# template.net
KiCad netlist of a schematic drawn in EAGLE
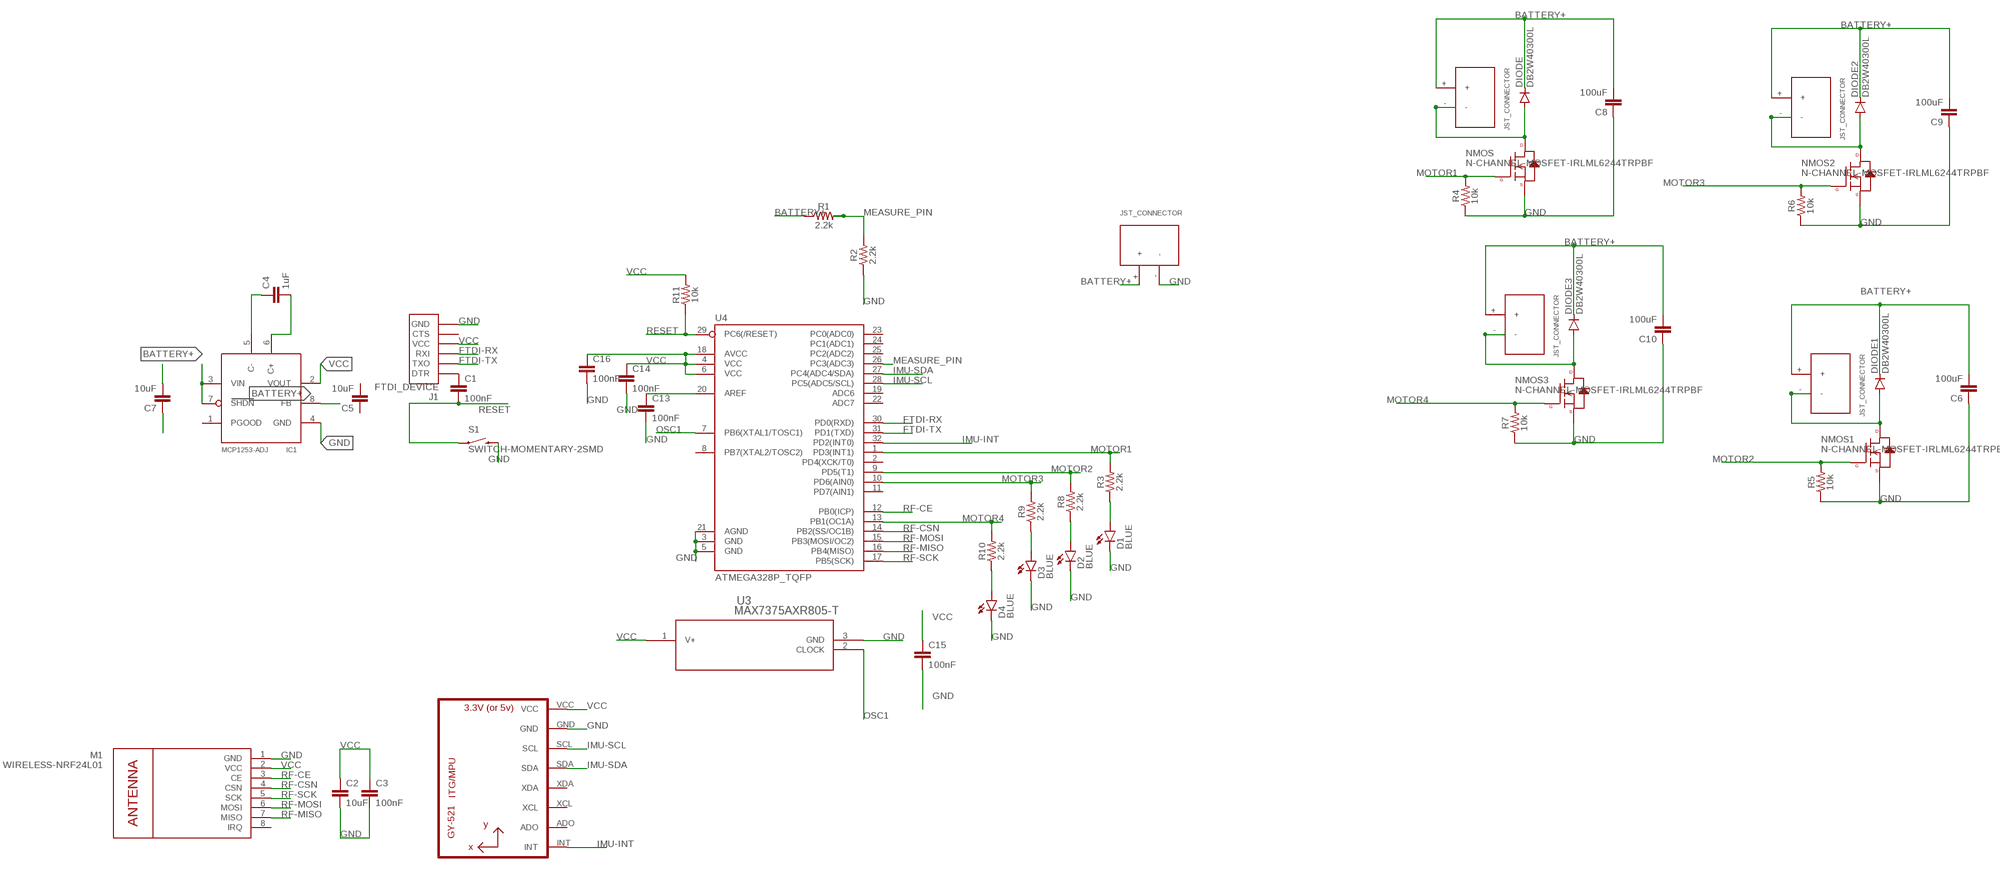
[diagram p0: schematic, sheet 1]

(export (version "E")
  (design (tool "Eeschema 10.0.6"))
  (components
    (comp (ref "C1")
      (value "100nF")
      (footprint "eagle-import:0603-CAP")
      (libsource (lib "eagle-import") (part "0.1UF-25V(+80/-20%)(0603)"))
    )
    (comp (ref "C2")
      (value "10uF")
      (footprint "eagle-import:0603-CAP")
      (libsource (lib "eagle-import") (part "CAP0603-CAP"))
    )
    (comp (ref "C3")
      (value "100nF")
      (footprint "eagle-import:0603-CAP")
      (libsource (lib "eagle-import") (part "CAP0603-CAP"))
    )
    (comp (ref "C4")
      (value "1uF")
      (footprint "eagle-import:0603-CAP")
      (libsource (lib "eagle-import") (part "0.1UF-25V(+80/-20%)(0603)"))
    )
    (comp (ref "C5")
      (value "10uF")
      (footprint "eagle-import:0603-CAP")
      (libsource (lib "eagle-import") (part "0.1UF-25V(+80/-20%)(0603)"))
    )
    (comp (ref "C6")
      (value "100uF")
      (footprint "eagle-import:1206")
      (libsource (lib "eagle-import") (part "CAP1206"))
    )
    (comp (ref "C7")
      (value "10uF")
      (footprint "eagle-import:0603-CAP")
      (libsource (lib "eagle-import") (part "0.1UF-25V(+80/-20%)(0603)"))
    )
    (comp (ref "C8")
      (value "100uF")
      (footprint "eagle-import:1206")
      (libsource (lib "eagle-import") (part "CAP1206"))
    )
    (comp (ref "C9")
      (value "100uF")
      (footprint "eagle-import:1206")
      (libsource (lib "eagle-import") (part "CAP1206"))
    )
    (comp (ref "C10")
      (value "100uF")
      (footprint "eagle-import:1206")
      (libsource (lib "eagle-import") (part "CAP1206"))
    )
    (comp (ref "C13")
      (value "100nF")
      (footprint "eagle-import:0603-CAP")
      (libsource (lib "eagle-import") (part "CAP0603-CAP"))
    )
    (comp (ref "C14")
      (value "100nF")
      (footprint "eagle-import:0603-CAP")
      (libsource (lib "eagle-import") (part "CAP0603-CAP"))
    )
    (comp (ref "C15")
      (value "100nF")
      (footprint "eagle-import:0603-CAP")
      (libsource (lib "eagle-import") (part "0.1UF-25V(+80/-20%)(0603)"))
    )
    (comp (ref "C16")
      (value "100nF")
      (footprint "eagle-import:0603-CAP")
      (libsource (lib "eagle-import") (part "CAP0603-CAP"))
    )
    (comp (ref "D1")
      (value "BLUE")
      (footprint "eagle-import:LED-0603")
      (fields (field (name "SPICEPREFIX") "D"))
      (libsource (lib "eagle-import") (part "LED-BLUE0603"))
    )
    (comp (ref "D2")
      (value "BLUE")
      (footprint "eagle-import:LED-0603")
      (libsource (lib "eagle-import") (part "LED-BLUE0603"))
    )
    (comp (ref "D3")
      (value "BLUE")
      (footprint "eagle-import:LED-0603")
      (libsource (lib "eagle-import") (part "LED-BLUE0603"))
    )
    (comp (ref "D4")
      (value "BLUE")
      (footprint "eagle-import:LED-0603")
      (libsource (lib "eagle-import") (part "LED-BLUE0603"))
    )
    (comp (ref "DIODE")
      (value "DB2W40300L")
      (footprint "eagle-import:MINI2-F3-B")
      (libsource (lib "eagle-import") (part "DB2W40300L"))
    )
    (comp (ref "DIODE1")
      (value "DB2W40300L")
      (footprint "eagle-import:MINI2-F3-B")
      (libsource (lib "eagle-import") (part "DB2W40300L"))
    )
    (comp (ref "DIODE2")
      (value "DB2W40300L")
      (footprint "eagle-import:MINI2-F3-B")
      (libsource (lib "eagle-import") (part "DB2W40300L"))
    )
    (comp (ref "DIODE3")
      (value "DB2W40300L")
      (footprint "eagle-import:MINI2-F3-B")
      (libsource (lib "eagle-import") (part "DB2W40300L"))
    )
    (comp (ref "IC1")
      (value "MCP1253-ADJ")
      (footprint "eagle-import:MSOP8")
      (libsource (lib "eagle-import") (part "MCP1253-ADJ"))
    )
    (comp (ref "J1")
      (value "FTDI_DEVICE")
      (footprint "eagle-import:FTDI_DEVICE_SIDE")
      (libsource (lib "eagle-import") (part "FTDI_DEVICE"))
    )
    (comp (ref "M1")
      (value "WIRELESS-NRF24L01")
      (footprint "eagle-import:WIRELESS-NRF24L01")
      (libsource (lib "eagle-import") (part "WIRELESS-NRF24L01"))
    )
    (comp (ref "MOTOR1")
      (value "JST_CONNECTOR_FEMALE")
      (footprint "eagle-import:JST_CONNECTOR_FEMALE")
      (libsource (lib "eagle-import") (part "JST_CONNECTOR_FEMALE"))
    )
    (comp (ref "MOTOR2")
      (value "JST_CONNECTOR_FEMALE")
      (footprint "eagle-import:JST_CONNECTOR_FEMALE")
      (libsource (lib "eagle-import") (part "JST_CONNECTOR_FEMALE"))
    )
    (comp (ref "MOTOR3")
      (value "JST_CONNECTOR_FEMALE")
      (footprint "eagle-import:JST_CONNECTOR_FEMALE")
      (libsource (lib "eagle-import") (part "JST_CONNECTOR_FEMALE"))
    )
    (comp (ref "MOTOR4")
      (value "JST_CONNECTOR_FEMALE")
      (footprint "eagle-import:JST_CONNECTOR_FEMALE")
      (libsource (lib "eagle-import") (part "JST_CONNECTOR_FEMALE"))
    )
    (comp (ref "NMOS")
      (value "N-CHANNEL-MOSFET-IRLML6244TRPBF")
      (footprint "eagle-import:SOT23-3")
      (libsource (lib "eagle-import") (part "N-CHANNEL-MOSFET-IRLML6244TRPBF"))
    )
    (comp (ref "NMOS1")
      (value "N-CHANNEL-MOSFET-IRLML6244TRPBF")
      (footprint "eagle-import:SOT23-3")
      (libsource (lib "eagle-import") (part "N-CHANNEL-MOSFET-IRLML6244TRPBF"))
    )
    (comp (ref "NMOS2")
      (value "N-CHANNEL-MOSFET-IRLML6244TRPBF")
      (footprint "eagle-import:SOT23-3")
      (libsource (lib "eagle-import") (part "N-CHANNEL-MOSFET-IRLML6244TRPBF"))
    )
    (comp (ref "NMOS3")
      (value "N-CHANNEL-MOSFET-IRLML6244TRPBF")
      (footprint "eagle-import:SOT23-3")
      (libsource (lib "eagle-import") (part "N-CHANNEL-MOSFET-IRLML6244TRPBF"))
    )
    (comp (ref "R1")
      (value "2.2k")
      (footprint "eagle-import:0603")
      (libsource (lib "eagle-import") (part "2.2KOHM-0603-1/10W-1%"))
    )
    (comp (ref "R2")
      (value "2.2k")
      (footprint "eagle-import:0603")
      (libsource (lib "eagle-import") (part "2.2KOHM-0603-1/10W-1%"))
    )
    (comp (ref "R3")
      (value "2.2k")
      (footprint "eagle-import:0603")
      (fields (field (name "SPICEPREFIX") "R"))
      (libsource (lib "eagle-import") (part "2.2KOHM-0603-1/10W-1%"))
    )
    (comp (ref "R4")
      (value "10k")
      (footprint "eagle-import:0603")
      (libsource (lib "eagle-import") (part "2.2KOHM-0603-1/10W-1%"))
    )
    (comp (ref "R5")
      (value "10k")
      (footprint "eagle-import:0603")
      (libsource (lib "eagle-import") (part "2.2KOHM-0603-1/10W-1%"))
    )
    (comp (ref "R6")
      (value "10k")
      (footprint "eagle-import:0603")
      (libsource (lib "eagle-import") (part "2.2KOHM-0603-1/10W-1%"))
    )
    (comp (ref "R7")
      (value "10k")
      (footprint "eagle-import:0603")
      (libsource (lib "eagle-import") (part "2.2KOHM-0603-1/10W-1%"))
    )
    (comp (ref "R8")
      (value "2.2k")
      (footprint "eagle-import:0603")
      (libsource (lib "eagle-import") (part "2.2KOHM-0603-1/10W-1%"))
    )
    (comp (ref "R9")
      (value "2.2k")
      (footprint "eagle-import:0603")
      (libsource (lib "eagle-import") (part "2.2KOHM-0603-1/10W-1%"))
    )
    (comp (ref "R10")
      (value "2.2k")
      (footprint "eagle-import:0603")
      (libsource (lib "eagle-import") (part "2.2KOHM-0603-1/10W-1%"))
    )
    (comp (ref "R11")
      (value "10k")
      (footprint "eagle-import:0603")
      (libsource (lib "eagle-import") (part "2.2KOHM-0603-1/10W-1%"))
    )
    (comp (ref "S1")
      (value "SWITCH-MOMENTARY-2SMD")
      (footprint "eagle-import:TACTILE-SWITCH-SMD")
      (libsource (lib "eagle-import") (part "SWITCH-MOMENTARY-2SMD"))
    )
    (comp (ref "U$1")
      (value "JST_CONNECTOR_FEMALE")
      (footprint "eagle-import:JST_CONNECTOR_FEMALE")
      (libsource (lib "eagle-import") (part "JST_CONNECTOR_FEMALE"))
    )
    (comp (ref "U2")
      (value "GY-521MPU6050")
      (footprint "eagle-import:GY-521")
      (libsource (lib "eagle-import") (part "GY-521MPU6050"))
    )
    (comp (ref "U3")
      (value "MAX7375AXR805-T")
      (footprint "eagle-import:21-0075D")
      (fields (field (name "MF") "Maxim Integrated") (field (name "MP") "MAX7375AXR805+T"))
      (libsource (lib "eagle-import") (part "MAX7375AXR805-T"))
    )
    (comp (ref "U4")
      (value "ATMEGA328P_TQFP")
      (footprint "eagle-import:TQFP32-08")
      (libsource (lib "eagle-import") (part "ATMEGA328P_TQFP"))
    )
  )
  (nets
    (net (code "1") (name "BATTERY+") (class "Default")
      (node (ref "C10") (pin "2") (pinfunction "2_2") (pintype "passive"))
      (node (ref "C6") (pin "2") (pinfunction "2_2") (pintype "passive"))
      (node (ref "C7") (pin "2") (pinfunction "2_2") (pintype "passive"))
      (node (ref "C8") (pin "2") (pinfunction "2_2") (pintype "passive"))
      (node (ref "C9") (pin "2") (pinfunction "2_2") (pintype "passive"))
      (node (ref "DIODE") (pin "NEG") (pinfunction "GPIN_NEG") (pintype "passive"))
      (node (ref "DIODE1") (pin "NEG") (pinfunction "GPIN_NEG") (pintype "passive"))
      (node (ref "DIODE2") (pin "NEG") (pinfunction "GPIN_NEG") (pintype "passive"))
      (node (ref "DIODE3") (pin "NEG") (pinfunction "GPIN_NEG") (pintype "passive"))
      (node (ref "IC1") (pin "3") (pinfunction "VIN_3") (pintype "power_in"))
      (node (ref "IC1") (pin "7") (pinfunction "SHDN_7") (pintype "input"))
      (node (ref "IC1") (pin "8") (pinfunction "FB_8") (pintype "input"))
      (node (ref "MOTOR1") (pin "+") (pinfunction "+_+") (pintype "bidirectional"))
      (node (ref "MOTOR2") (pin "+") (pinfunction "+_+") (pintype "bidirectional"))
      (node (ref "MOTOR3") (pin "+") (pinfunction "+_+") (pintype "bidirectional"))
      (node (ref "MOTOR4") (pin "+") (pinfunction "+_+") (pintype "bidirectional"))
      (node (ref "R1") (pin "1") (pinfunction "1_1") (pintype "passive"))
      (node (ref "U$1") (pin "+") (pinfunction "+_+") (pintype "bidirectional"))
    )
    (net (code "2") (name "FTDI-RX") (class "Default")
      (node (ref "J1") (pin "P$3") (pinfunction "RXI_P$3") (pintype "bidirectional"))
      (node (ref "U4") (pin "30") (pinfunction "PD0(RXD)_30") (pintype "bidirectional"))
    )
    (net (code "3") (name "FTDI-TX") (class "Default")
      (node (ref "J1") (pin "P$2") (pinfunction "TXO_P$2") (pintype "bidirectional"))
      (node (ref "U4") (pin "31") (pinfunction "PD1(TXD)_31") (pintype "bidirectional"))
    )
    (net (code "4") (name "GND") (class "Default")
      (node (ref "C10") (pin "1") (pinfunction "1_1") (pintype "passive"))
      (node (ref "C13") (pin "2") (pinfunction "2_2") (pintype "passive"))
      (node (ref "C14") (pin "2") (pinfunction "2_2") (pintype "passive"))
      (node (ref "C15") (pin "2") (pinfunction "2_2") (pintype "passive"))
      (node (ref "C16") (pin "2") (pinfunction "2_2") (pintype "passive"))
      (node (ref "C2") (pin "2") (pinfunction "2_2") (pintype "passive"))
      (node (ref "C3") (pin "2") (pinfunction "2_2") (pintype "passive"))
      (node (ref "C6") (pin "1") (pinfunction "1_1") (pintype "passive"))
      (node (ref "C7") (pin "1") (pinfunction "1_1") (pintype "passive"))
      (node (ref "C8") (pin "1") (pinfunction "1_1") (pintype "passive"))
      (node (ref "C9") (pin "1") (pinfunction "1_1") (pintype "passive"))
      (node (ref "D1") (pin "C") (pinfunction "C_C") (pintype "passive"))
      (node (ref "D2") (pin "C") (pinfunction "C_C") (pintype "passive"))
      (node (ref "D3") (pin "C") (pinfunction "C_C") (pintype "passive"))
      (node (ref "D4") (pin "C") (pinfunction "C_C") (pintype "passive"))
      (node (ref "IC1") (pin "4") (pinfunction "GND_4") (pintype "power_in"))
      (node (ref "J1") (pin "P$6") (pinfunction "GND_P$6") (pintype "bidirectional"))
      (node (ref "M1") (pin "1") (pinfunction "GND_1") (pintype "power_in"))
      (node (ref "NMOS") (pin "2") (pinfunction "S_2") (pintype "passive"))
      (node (ref "NMOS1") (pin "2") (pinfunction "S_2") (pintype "passive"))
      (node (ref "NMOS2") (pin "2") (pinfunction "S_2") (pintype "passive"))
      (node (ref "NMOS3") (pin "2") (pinfunction "S_2") (pintype "passive"))
      (node (ref "R2") (pin "1") (pinfunction "1_1") (pintype "passive"))
      (node (ref "R4") (pin "1") (pinfunction "1_1") (pintype "passive"))
      (node (ref "R5") (pin "1") (pinfunction "1_1") (pintype "passive"))
      (node (ref "R6") (pin "1") (pinfunction "1_1") (pintype "passive"))
      (node (ref "R7") (pin "1") (pinfunction "1_1") (pintype "passive"))
      (node (ref "S1") (pin "3") (pinfunction "2_3") (pintype "passive"))
      (node (ref "U$1") (pin "-") (pinfunction "-_-") (pintype "bidirectional"))
      (node (ref "U2") (pin "GND") (pinfunction "GND_GND") (pintype "bidirectional"))
      (node (ref "U3") (pin "3") (pinfunction "GND_3") (pintype "power_in"))
      (node (ref "U4") (pin "21") (pinfunction "AGND_21") (pintype "bidirectional"))
      (node (ref "U4") (pin "3") (pinfunction "GND_3") (pintype "bidirectional"))
      (node (ref "U4") (pin "5") (pinfunction "GND_5") (pintype "bidirectional"))
    )
    (net (code "5") (name "IMU-INT") (class "Default")
      (node (ref "U2") (pin "INT") (pinfunction "INT_INT") (pintype "bidirectional"))
      (node (ref "U4") (pin "32") (pinfunction "PD2(INT0)_32") (pintype "bidirectional"))
    )
    (net (code "6") (name "IMU-SCL") (class "Default")
      (node (ref "U2") (pin "SCL") (pinfunction "SCL_SCL") (pintype "bidirectional"))
      (node (ref "U4") (pin "28") (pinfunction "PC5(ADC5/SCL)_28") (pintype "bidirectional"))
    )
    (net (code "7") (name "IMU-SDA") (class "Default")
      (node (ref "U2") (pin "SDA") (pinfunction "SDA_SDA") (pintype "bidirectional"))
      (node (ref "U4") (pin "27") (pinfunction "PC4(ADC4/SDA)_27") (pintype "bidirectional"))
    )
    (net (code "8") (name "MEASURE_PIN") (class "Default")
      (node (ref "R1") (pin "2") (pinfunction "2_2") (pintype "passive"))
      (node (ref "R2") (pin "2") (pinfunction "2_2") (pintype "passive"))
      (node (ref "U4") (pin "26") (pinfunction "PC3(ADC3)_26") (pintype "bidirectional"))
    )
    (net (code "9") (name "MOTOR1") (class "Default")
      (node (ref "NMOS") (pin "1") (pinfunction "G_1") (pintype "passive"))
      (node (ref "R3") (pin "2") (pinfunction "2_2") (pintype "passive"))
      (node (ref "R4") (pin "2") (pinfunction "2_2") (pintype "passive"))
      (node (ref "U4") (pin "1") (pinfunction "PD3(INT1)_1") (pintype "bidirectional"))
    )
    (net (code "10") (name "MOTOR2") (class "Default")
      (node (ref "NMOS1") (pin "1") (pinfunction "G_1") (pintype "passive"))
      (node (ref "R5") (pin "2") (pinfunction "2_2") (pintype "passive"))
      (node (ref "R8") (pin "2") (pinfunction "2_2") (pintype "passive"))
      (node (ref "U4") (pin "9") (pinfunction "PD5(T1)_9") (pintype "bidirectional"))
    )
    (net (code "11") (name "MOTOR3") (class "Default")
      (node (ref "NMOS2") (pin "1") (pinfunction "G_1") (pintype "passive"))
      (node (ref "R6") (pin "2") (pinfunction "2_2") (pintype "passive"))
      (node (ref "R9") (pin "2") (pinfunction "2_2") (pintype "passive"))
      (node (ref "U4") (pin "10") (pinfunction "PD6(AIN0)_10") (pintype "bidirectional"))
    )
    (net (code "12") (name "MOTOR4") (class "Default")
      (node (ref "NMOS3") (pin "1") (pinfunction "G_1") (pintype "passive"))
      (node (ref "R10") (pin "2") (pinfunction "2_2") (pintype "passive"))
      (node (ref "R7") (pin "2") (pinfunction "2_2") (pintype "passive"))
      (node (ref "U4") (pin "13") (pinfunction "PB1(OC1A)_13") (pintype "bidirectional"))
    )
    (net (code "13") (name "Net-(D1-PadA)") (class "Default")
      (node (ref "D1") (pin "A") (pinfunction "A_A") (pintype "passive"))
      (node (ref "R3") (pin "1") (pinfunction "1_1") (pintype "passive"))
    )
    (net (code "14") (name "Net-(D2-PadA)") (class "Default")
      (node (ref "D2") (pin "A") (pinfunction "A_A") (pintype "passive"))
      (node (ref "R8") (pin "1") (pinfunction "1_1") (pintype "passive"))
    )
    (net (code "15") (name "Net-(D3-PadA)") (class "Default")
      (node (ref "D3") (pin "A") (pinfunction "A_A") (pintype "passive"))
      (node (ref "R9") (pin "1") (pinfunction "1_1") (pintype "passive"))
    )
    (net (code "16") (name "Net-(D4-PadA)") (class "Default")
      (node (ref "D4") (pin "A") (pinfunction "A_A") (pintype "passive"))
      (node (ref "R10") (pin "1") (pinfunction "1_1") (pintype "passive"))
    )
    (net (code "17") (name "Net-(DIODE-PPIN)") (class "Default")
      (node (ref "DIODE") (pin "POS") (pinfunction "PPIN_POS") (pintype "passive"))
      (node (ref "MOTOR1") (pin "-") (pinfunction "-_-") (pintype "bidirectional"))
      (node (ref "NMOS") (pin "3") (pinfunction "D_3") (pintype "passive"))
    )
    (net (code "18") (name "Net-(DIODE1-PPIN)") (class "Default")
      (node (ref "DIODE1") (pin "POS") (pinfunction "PPIN_POS") (pintype "passive"))
      (node (ref "MOTOR2") (pin "-") (pinfunction "-_-") (pintype "bidirectional"))
      (node (ref "NMOS1") (pin "3") (pinfunction "D_3") (pintype "passive"))
    )
    (net (code "19") (name "Net-(DIODE2-PPIN)") (class "Default")
      (node (ref "DIODE2") (pin "POS") (pinfunction "PPIN_POS") (pintype "passive"))
      (node (ref "MOTOR3") (pin "-") (pinfunction "-_-") (pintype "bidirectional"))
      (node (ref "NMOS2") (pin "3") (pinfunction "D_3") (pintype "passive"))
    )
    (net (code "20") (name "Net-(DIODE3-PPIN)") (class "Default")
      (node (ref "DIODE3") (pin "POS") (pinfunction "PPIN_POS") (pintype "passive"))
      (node (ref "MOTOR4") (pin "-") (pinfunction "-_-") (pintype "bidirectional"))
      (node (ref "NMOS3") (pin "3") (pinfunction "D_3") (pintype "passive"))
    )
    (net (code "21") (name "Net-(IC1-C+)") (class "Default")
      (node (ref "C4") (pin "2") (pinfunction "2_2") (pintype "passive"))
      (node (ref "IC1") (pin "6") (pinfunction "C+_6") (pintype "passive"))
    )
    (net (code "22") (name "Net-(IC1-C-)") (class "Default")
      (node (ref "C4") (pin "1") (pinfunction "1_1") (pintype "passive"))
      (node (ref "IC1") (pin "5") (pinfunction "C-_5") (pintype "passive"))
    )
    (net (code "23") (name "Net-(J1-DTR)") (class "Default")
      (node (ref "C1") (pin "1") (pinfunction "1_1") (pintype "passive"))
      (node (ref "J1") (pin "P$1") (pinfunction "DTR_P$1") (pintype "bidirectional"))
    )
    (net (code "24") (name "Net-(U4-AREF)") (class "Default")
      (node (ref "C13") (pin "1") (pinfunction "1_1") (pintype "passive"))
      (node (ref "U4") (pin "20") (pinfunction "AREF_20") (pintype "bidirectional"))
    )
    (net (code "25") (name "OSC1") (class "Default")
      (node (ref "U3") (pin "2") (pinfunction "CLOCK_2") (pintype "output"))
      (node (ref "U4") (pin "7") (pinfunction "PB6(XTAL1/TOSC1)_7") (pintype "bidirectional"))
    )
    (net (code "26") (name "RESET") (class "Default")
      (node (ref "C1") (pin "2") (pinfunction "2_2") (pintype "passive"))
      (node (ref "R11") (pin "1") (pinfunction "1_1") (pintype "passive"))
      (node (ref "S1") (pin "1") (pinfunction "1_1") (pintype "passive"))
      (node (ref "U4") (pin "29") (pinfunction "PC6(/RESET)_29") (pintype "bidirectional"))
    )
    (net (code "27") (name "RF-CE") (class "Default")
      (node (ref "M1") (pin "3") (pinfunction "CE_3") (pintype "bidirectional"))
      (node (ref "U4") (pin "12") (pinfunction "PB0(ICP)_12") (pintype "bidirectional"))
    )
    (net (code "28") (name "RF-CSN") (class "Default")
      (node (ref "M1") (pin "4") (pinfunction "CSN_4") (pintype "bidirectional"))
      (node (ref "U4") (pin "14") (pinfunction "PB2(SS/OC1B)_14") (pintype "bidirectional"))
    )
    (net (code "29") (name "RF-MISO") (class "Default")
      (node (ref "M1") (pin "7") (pinfunction "MISO_7") (pintype "bidirectional"))
      (node (ref "U4") (pin "16") (pinfunction "PB4(MISO)_16") (pintype "bidirectional"))
    )
    (net (code "30") (name "RF-MOSI") (class "Default")
      (node (ref "M1") (pin "6") (pinfunction "MOSI_6") (pintype "bidirectional"))
      (node (ref "U4") (pin "15") (pinfunction "PB3(MOSI/OC2)_15") (pintype "bidirectional"))
    )
    (net (code "31") (name "RF-SCK") (class "Default")
      (node (ref "M1") (pin "5") (pinfunction "SCK_5") (pintype "bidirectional"))
      (node (ref "U4") (pin "17") (pinfunction "PB5(SCK)_17") (pintype "bidirectional"))
    )
    (net (code "32") (name "VCC") (class "Default")
      (node (ref "C14") (pin "1") (pinfunction "1_1") (pintype "passive"))
      (node (ref "C15") (pin "1") (pinfunction "1_1") (pintype "passive"))
      (node (ref "C16") (pin "1") (pinfunction "1_1") (pintype "passive"))
      (node (ref "C2") (pin "1") (pinfunction "1_1") (pintype "passive"))
      (node (ref "C3") (pin "1") (pinfunction "1_1") (pintype "passive"))
      (node (ref "IC1") (pin "2") (pinfunction "VOUT_2") (pintype "output"))
      (node (ref "J1") (pin "P$4") (pinfunction "VCC_P$4") (pintype "bidirectional"))
      (node (ref "M1") (pin "2") (pinfunction "VCC_2") (pintype "power_in"))
      (node (ref "R11") (pin "2") (pinfunction "2_2") (pintype "passive"))
      (node (ref "U2") (pin "VCC") (pinfunction "VCC_VCC") (pintype "bidirectional"))
      (node (ref "U3") (pin "1") (pinfunction "V+_1") (pintype "power_in"))
      (node (ref "U4") (pin "18") (pinfunction "AVCC_18") (pintype "bidirectional"))
      (node (ref "U4") (pin "4") (pinfunction "VCC_4") (pintype "bidirectional"))
      (node (ref "U4") (pin "6") (pinfunction "VCC_6") (pintype "bidirectional"))
    )
    (net (code "33") (name "unconnected-(C5-Pad1)") (class "Default")
      (node (ref "C5") (pin "1") (pinfunction "1_1") (pintype "passive"))
    )
    (net (code "34") (name "unconnected-(C5-Pad2)") (class "Default")
      (node (ref "C5") (pin "2") (pinfunction "2_2") (pintype "passive"))
    )
    (net (code "35") (name "unconnected-(IC1-PGOOD-Pad1)") (class "Default")
      (node (ref "IC1") (pin "1") (pinfunction "PGOOD_1") (pintype "output"))
    )
    (net (code "36") (name "unconnected-(J1-CTS-PadP$5)") (class "Default")
      (node (ref "J1") (pin "P$5") (pinfunction "CTS_P$5") (pintype "bidirectional"))
    )
    (net (code "37") (name "unconnected-(M1-IRQ-Pad8)") (class "Default")
      (node (ref "M1") (pin "8") (pinfunction "IRQ_8") (pintype "bidirectional"))
    )
    (net (code "38") (name "unconnected-(U2-PadADO)") (class "Default")
      (node (ref "U2") (pin "ADO") (pinfunction "ADO_ADO") (pintype "bidirectional"))
    )
    (net (code "39") (name "unconnected-(U2-PadXCL)") (class "Default")
      (node (ref "U2") (pin "XCL") (pinfunction "XCL_XCL") (pintype "bidirectional"))
    )
    (net (code "40") (name "unconnected-(U2-PadXDA)") (class "Default")
      (node (ref "U2") (pin "XDA") (pinfunction "XDA_XDA") (pintype "bidirectional"))
    )
    (net (code "41") (name "unconnected-(U4-ADC6-Pad19)") (class "Default")
      (node (ref "U4") (pin "19") (pinfunction "ADC6_19") (pintype "bidirectional"))
    )
    (net (code "42") (name "unconnected-(U4-ADC7-Pad22)") (class "Default")
      (node (ref "U4") (pin "22") (pinfunction "ADC7_22") (pintype "bidirectional"))
    )
    (net (code "43") (name "unconnected-(U4-PB7(XTAL2{slash}TOSC2)-Pad8)") (class "Default")
      (node (ref "U4") (pin "8") (pinfunction "PB7(XTAL2/TOSC2)_8") (pintype "bidirectional"))
    )
    (net (code "44") (name "unconnected-(U4-PC0(ADC0)-Pad23)") (class "Default")
      (node (ref "U4") (pin "23") (pinfunction "PC0(ADC0)_23") (pintype "bidirectional"))
    )
    (net (code "45") (name "unconnected-(U4-PC1(ADC1)-Pad24)") (class "Default")
      (node (ref "U4") (pin "24") (pinfunction "PC1(ADC1)_24") (pintype "bidirectional"))
    )
    (net (code "46") (name "unconnected-(U4-PC2(ADC2)-Pad25)") (class "Default")
      (node (ref "U4") (pin "25") (pinfunction "PC2(ADC2)_25") (pintype "bidirectional"))
    )
    (net (code "47") (name "unconnected-(U4-PD4(XCK{slash}T0)-Pad2)") (class "Default")
      (node (ref "U4") (pin "2") (pinfunction "PD4(XCK/T0)_2") (pintype "bidirectional"))
    )
    (net (code "48") (name "unconnected-(U4-PD7(AIN1)-Pad11)") (class "Default")
      (node (ref "U4") (pin "11") (pinfunction "PD7(AIN1)_11") (pintype "bidirectional"))
    )
  )
)
